# MCU_Radios_and_Sensors_SchDoc.net
KiCad netlist of a schematic drawn in Altium Designer
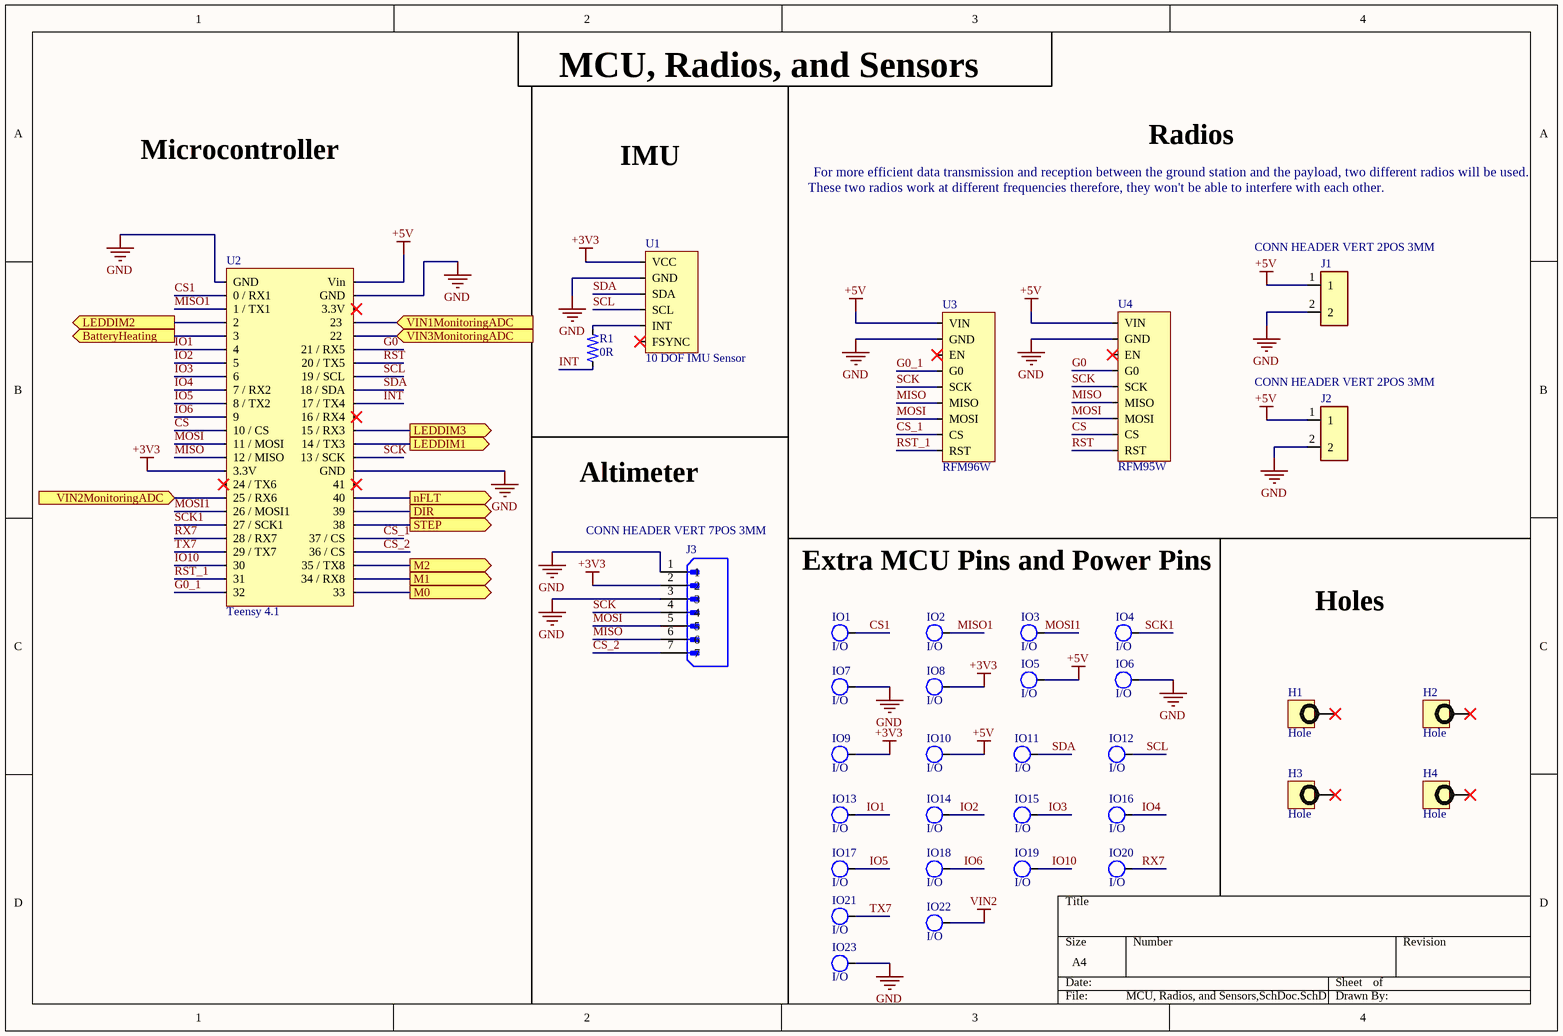
[diagram p0: MCU, Radios, and Sensors,SchDoc.SchDoc]

(export (version "E")
  (design (tool "Eeschema 10.0.6"))
  (components
    (comp (ref "H1") (value "Hole") (footprint "M3 Holes") (libsource (lib "MRT SCH Library") (part "Hole")))
    (comp (ref "H2") (value "Hole") (footprint "M3 Holes") (libsource (lib "MRT SCH Library") (part "Hole")))
    (comp (ref "H3") (value "Hole") (footprint "M3 Holes") (libsource (lib "MRT SCH Library") (part "Hole")))
    (comp (ref "H4") (value "Hole") (footprint "M3 Holes") (libsource (lib "MRT SCH Library") (part "Hole")))
    (comp (ref "IO1") (value "I/O") (footprint "Pins") (libsource (lib "Payload schlib") (part "I/O")))
    (comp (ref "IO2") (value "I/O") (footprint "Pins") (libsource (lib "Payload schlib") (part "I/O")))
    (comp (ref "IO3") (value "I/O") (footprint "Pins") (libsource (lib "Payload schlib") (part "I/O")))
    (comp (ref "IO4") (value "I/O") (footprint "Pins") (libsource (lib "Payload schlib") (part "I/O")))
    (comp (ref "IO5") (value "I/O") (footprint "Pins") (libsource (lib "Payload schlib") (part "I/O")))
    (comp (ref "IO6") (value "I/O") (footprint "Pins") (libsource (lib "Payload schlib") (part "I/O")))
    (comp (ref "IO7") (value "I/O") (footprint "Pins") (libsource (lib "Payload schlib") (part "I/O")))
    (comp (ref "IO8") (value "I/O") (footprint "Pins") (libsource (lib "Payload schlib") (part "I/O")))
    (comp (ref "IO9") (value "I/O") (footprint "Pins") (libsource (lib "Payload schlib") (part "I/O")))
    (comp (ref "IO10") (value "I/O") (footprint "Pins") (libsource (lib "Payload schlib") (part "I/O")))
    (comp (ref "IO11") (value "I/O") (footprint "Pins") (libsource (lib "Payload schlib") (part "I/O")))
    (comp (ref "IO12") (value "I/O") (footprint "Pins") (libsource (lib "Payload schlib") (part "I/O")))
    (comp (ref "IO13") (value "I/O") (footprint "Pins") (libsource (lib "Payload schlib") (part "I/O")))
    (comp (ref "IO14") (value "I/O") (footprint "Pins") (libsource (lib "Payload schlib") (part "I/O")))
    (comp (ref "IO15") (value "I/O") (footprint "Pins") (libsource (lib "Payload schlib") (part "I/O")))
    (comp (ref "IO16") (value "I/O") (footprint "Pins") (libsource (lib "Payload schlib") (part "I/O")))
    (comp (ref "IO17") (value "I/O") (footprint "Pins") (libsource (lib "Payload schlib") (part "I/O")))
    (comp (ref "IO18") (value "I/O") (footprint "Pins") (libsource (lib "Payload schlib") (part "I/O")))
    (comp (ref "IO19") (value "I/O") (footprint "Pins") (libsource (lib "Payload schlib") (part "I/O")))
    (comp (ref "IO20") (value "I/O") (footprint "Pins") (libsource (lib "Payload schlib") (part "I/O")))
    (comp (ref "IO21") (value "I/O") (footprint "Pins") (libsource (lib "Payload schlib") (part "I/O")))
    (comp (ref "IO22") (value "I/O") (footprint "Pins") (libsource (lib "Payload schlib") (part "I/O")))
    (comp (ref "IO23") (value "I/O") (footprint "Pins") (libsource (lib "Payload schlib") (part "I/O")))
    (comp (ref "J1")
      (value "CONN HEADER VERT 2POS 3MM")
      (footprint "CONN HEADER VERT 2POS 3MM")
      (description "Rectangular Power Connector, 2 Contact(s), Female, Solder Terminal")
      (fields (field (name "MF") "Molex") (field (name "MP") "0436500200"))
      (libsource (lib "Payload schlib") (part "0436500228"))
    )
    (comp (ref "J2")
      (value "CONN HEADER VERT 2POS 3MM")
      (footprint "CONN HEADER VERT 2POS 3MM")
      (description "Rectangular Power Connector, 2 Contact(s), Female, Solder Terminal")
      (fields (field (name "MF") "Molex") (field (name "MP") "0436500200"))
      (libsource (lib "Payload schlib") (part "0436500228"))
    )
    (comp (ref "J3")
      (value "CONN HEADER VERT 7POS 3MM")
      (footprint "MOLEX_436500728")
      (description "Connector Header Through Hole 7 position 0.118 (3.00mm)")
      (fields (field (name "MF") "Molex") (field (name "MP") "436500728"))
      (libsource (lib "Payload schlib") (part "436500728"))
    )
    (comp (ref "R1")
      (value "0R")
      (footprint "res 0805")
      (fields
        (field (name "MP") "2-2176053-2")
        (field (name "MF") "TE Connectivity")
        (field (name "TOLERANCE") "1%")
      )
      (libsource (lib "Payload schlib") (part "Resistor 0805"))
    )
    (comp (ref "U1")
      (value "10 DOF IMU Sensor")
      (footprint "10 DOF IMU Sensor")
      (description "10 DOF IMU Sensor, ICM20948 Onboard, Low Power, High Precision")
      (libsource (lib "Payload schlib") (part "10 DOF IMU Sensor"))
    )
    (comp (ref "U2")
      (value "Teensy 4.1")
      (footprint "Teensy 4.1")
      (description "iMXRT1062 Microcontroller Development Board 600MHz CPU 1GB RAM 8MB Flash")
      (fields (field (name "MANUFACTURER") "SparkFun") (field (name "MANUFACTURER PART NUMBER") "DEV-16771"))
      (libsource (lib "Payload schlib") (part "Teensy 4.1"))
    )
    (comp (ref "U3")
      (value "RFM96W")
      (footprint "RFM95W")
      (description "Banana Plug; Female to Multi-Stacking Banana Plug; Nickel Plated Brass")
      (fields
        (field (name "MANUFACTURER") "Adafruit Industries")
        (field (name "MANUFACTURER PART NUMBER") "3072")
      )
      (libsource (lib "Payload schlib") (part "RFM96W"))
    )
    (comp (ref "U4")
      (value "RFM95W")
      (footprint "RFM95W")
      (description "Adafruit RFM95W LoRa Radio Transceiver Breakout - 868 or 915 MHz")
      (fields
        (field (name "MANUFACTURER") "Adafruit Industries")
        (field (name "MANUFACTURER PART NUMBER") "3072")
      )
      (libsource (lib "Payload schlib") (part "RFM95W"))
    )
  )
  (nets
    (net (code "1") (name "+3V3") (class "Default")
      (node (ref "IO8") (pin "1") (pinfunction "1_1") (pintype "passive"))
      (node (ref "IO9") (pin "1") (pinfunction "1_1") (pintype "passive"))
      (node (ref "J3") (pin "2") (pinfunction "2_2") (pintype "passive"))
      (node (ref "U1") (pin "1") (pinfunction "VCC_1") (pintype "passive"))
      (node (ref "U2") (pin "15") (pinfunction "3.3V_15") (pintype "passive"))
    )
    (net (code "2") (name "+5V") (class "Default")
      (node (ref "IO10") (pin "1") (pinfunction "1_1") (pintype "passive"))
      (node (ref "IO5") (pin "1") (pinfunction "1_1") (pintype "passive"))
      (node (ref "J1") (pin "1") (pinfunction "1_1") (pintype "passive"))
      (node (ref "J2") (pin "1") (pinfunction "1_1") (pintype "passive"))
      (node (ref "U2") (pin "48") (pinfunction "Vin_48") (pintype "passive"))
      (node (ref "U3") (pin "1") (pinfunction "VIN_1") (pintype "passive"))
      (node (ref "U4") (pin "1") (pinfunction "VIN_1") (pintype "passive"))
    )
    (net (code "3") (name "/BatteryHeating") (class "Default")
      (node (ref "U2") (pin "5") (pinfunction "3_5") (pintype "passive"))
    )
    (net (code "4") (name "/CS") (class "Default")
      (node (ref "U2") (pin "12") (pinfunction "10_/_CS_12") (pintype "passive"))
      (node (ref "U4") (pin "8") (pinfunction "CS_8") (pintype "passive"))
    )
    (net (code "5") (name "/CS1") (class "Default")
      (node (ref "IO1") (pin "1") (pinfunction "1_1") (pintype "passive"))
      (node (ref "U2") (pin "2") (pinfunction "0_/_RX1_2") (pintype "passive"))
    )
    (net (code "6") (name "/CS_1") (class "Default")
      (node (ref "U2") (pin "29") (pinfunction "37_/_CS_29") (pintype "passive"))
      (node (ref "U3") (pin "8") (pinfunction "CS_8") (pintype "passive"))
    )
    (net (code "7") (name "/CS_2") (class "Default")
      (node (ref "J3") (pin "7") (pinfunction "7_7") (pintype "passive"))
      (node (ref "U2") (pin "28") (pinfunction "36_/_CS_28") (pintype "passive"))
    )
    (net (code "8") (name "/DIR") (class "Default")
      (node (ref "U2") (pin "31") (pinfunction "39_31") (pintype "passive"))
    )
    (net (code "9") (name "/G0") (class "Default")
      (node (ref "U2") (pin "43") (pinfunction "21_/_RX5_43") (pintype "passive"))
      (node (ref "U4") (pin "4") (pinfunction "G0_4") (pintype "passive"))
    )
    (net (code "10") (name "/G0_1") (class "Default")
      (node (ref "U2") (pin "24") (pinfunction "32_24") (pintype "passive"))
      (node (ref "U3") (pin "4") (pinfunction "G0_4") (pintype "passive"))
    )
    (net (code "11") (name "/INT") (class "Default")
      (node (ref "R1") (pin "1") (pinfunction "1_1") (pintype "passive"))
      (node (ref "U2") (pin "39") (pinfunction "17_/_TX4_39") (pintype "passive"))
    )
    (net (code "12") (name "/IO1") (class "Default")
      (node (ref "IO13") (pin "1") (pinfunction "1_1") (pintype "passive"))
      (node (ref "U2") (pin "6") (pinfunction "4_6") (pintype "passive"))
    )
    (net (code "13") (name "/IO2") (class "Default")
      (node (ref "IO14") (pin "1") (pinfunction "1_1") (pintype "passive"))
      (node (ref "U2") (pin "7") (pinfunction "5_7") (pintype "passive"))
    )
    (net (code "14") (name "/IO3") (class "Default")
      (node (ref "IO15") (pin "1") (pinfunction "1_1") (pintype "passive"))
      (node (ref "U2") (pin "8") (pinfunction "6_8") (pintype "passive"))
    )
    (net (code "15") (name "/IO4") (class "Default")
      (node (ref "IO16") (pin "1") (pinfunction "1_1") (pintype "passive"))
      (node (ref "U2") (pin "9") (pinfunction "7_/_RX2_9") (pintype "passive"))
    )
    (net (code "16") (name "/IO5") (class "Default")
      (node (ref "IO17") (pin "1") (pinfunction "1_1") (pintype "passive"))
      (node (ref "U2") (pin "10") (pinfunction "8_/_TX2_10") (pintype "passive"))
    )
    (net (code "17") (name "/IO6") (class "Default")
      (node (ref "IO18") (pin "1") (pinfunction "1_1") (pintype "passive"))
      (node (ref "U2") (pin "11") (pinfunction "9_11") (pintype "passive"))
    )
    (net (code "18") (name "/IO10") (class "Default")
      (node (ref "IO19") (pin "1") (pinfunction "1_1") (pintype "passive"))
      (node (ref "U2") (pin "22") (pinfunction "30_22") (pintype "passive"))
    )
    (net (code "19") (name "/LEDDIM1") (class "Default")
      (node (ref "U2") (pin "36") (pinfunction "14_/_TX3_36") (pintype "passive"))
    )
    (net (code "20") (name "/LEDDIM2") (class "Default")
      (node (ref "U2") (pin "4") (pinfunction "2_4") (pintype "passive"))
    )
    (net (code "21") (name "/LEDDIM3") (class "Default")
      (node (ref "U2") (pin "37") (pinfunction "15_/_RX3_37") (pintype "passive"))
    )
    (net (code "22") (name "/M0") (class "Default")
      (node (ref "U2") (pin "25") (pinfunction "33_25") (pintype "passive"))
    )
    (net (code "23") (name "/M1") (class "Default")
      (node (ref "U2") (pin "26") (pinfunction "34_/_RX8_26") (pintype "passive"))
    )
    (net (code "24") (name "/M2") (class "Default")
      (node (ref "U2") (pin "27") (pinfunction "35_/_TX8_27") (pintype "passive"))
    )
    (net (code "25") (name "/MISO") (class "Default")
      (node (ref "J3") (pin "6") (pinfunction "6_6") (pintype "passive"))
      (node (ref "U2") (pin "14") (pinfunction "12_/_MISO_14") (pintype "passive"))
      (node (ref "U3") (pin "6") (pinfunction "MISO_6") (pintype "passive"))
      (node (ref "U4") (pin "6") (pinfunction "MISO_6") (pintype "passive"))
    )
    (net (code "26") (name "/MISO1") (class "Default")
      (node (ref "IO2") (pin "1") (pinfunction "1_1") (pintype "passive"))
      (node (ref "U2") (pin "3") (pinfunction "1_/_TX1_3") (pintype "passive"))
    )
    (net (code "27") (name "/MOSI") (class "Default")
      (node (ref "J3") (pin "5") (pinfunction "5_5") (pintype "passive"))
      (node (ref "U2") (pin "13") (pinfunction "11_/_MOSI_13") (pintype "passive"))
      (node (ref "U3") (pin "7") (pinfunction "MOSI_7") (pintype "passive"))
      (node (ref "U4") (pin "7") (pinfunction "MOSI_7") (pintype "passive"))
    )
    (net (code "28") (name "/MOSI1") (class "Default")
      (node (ref "IO3") (pin "1") (pinfunction "1_1") (pintype "passive"))
      (node (ref "U2") (pin "18") (pinfunction "26_/_MOSI1_18") (pintype "passive"))
    )
    (net (code "29") (name "/RST") (class "Default")
      (node (ref "U2") (pin "42") (pinfunction "20_/_TX5_42") (pintype "passive"))
      (node (ref "U4") (pin "9") (pinfunction "RST_9") (pintype "passive"))
    )
    (net (code "30") (name "/RST_1") (class "Default")
      (node (ref "U2") (pin "23") (pinfunction "31_23") (pintype "passive"))
      (node (ref "U3") (pin "9") (pinfunction "RST_9") (pintype "passive"))
    )
    (net (code "31") (name "/RX7") (class "Default")
      (node (ref "IO20") (pin "1") (pinfunction "1_1") (pintype "passive"))
      (node (ref "U2") (pin "20") (pinfunction "28_/_RX7_20") (pintype "passive"))
    )
    (net (code "32") (name "/SCK") (class "Default")
      (node (ref "J3") (pin "4") (pinfunction "4_4") (pintype "passive"))
      (node (ref "U2") (pin "35") (pinfunction "13_/_SCK_35") (pintype "passive"))
      (node (ref "U3") (pin "5") (pinfunction "SCK_5") (pintype "passive"))
      (node (ref "U4") (pin "5") (pinfunction "SCK_5") (pintype "passive"))
    )
    (net (code "33") (name "/SCK1") (class "Default")
      (node (ref "IO4") (pin "1") (pinfunction "1_1") (pintype "passive"))
      (node (ref "U2") (pin "19") (pinfunction "27_/_SCK1_19") (pintype "passive"))
    )
    (net (code "34") (name "/SCL") (class "Default")
      (node (ref "IO12") (pin "1") (pinfunction "1_1") (pintype "passive"))
      (node (ref "U1") (pin "4") (pinfunction "SCL_4") (pintype "passive"))
      (node (ref "U2") (pin "41") (pinfunction "19_/_SCL_41") (pintype "passive"))
    )
    (net (code "35") (name "/SDA") (class "Default")
      (node (ref "IO11") (pin "1") (pinfunction "1_1") (pintype "passive"))
      (node (ref "U1") (pin "3") (pinfunction "SDA_3") (pintype "passive"))
      (node (ref "U2") (pin "40") (pinfunction "18_/_SDA_40") (pintype "passive"))
    )
    (net (code "36") (name "/STEP") (class "Default")
      (node (ref "U2") (pin "30") (pinfunction "38_30") (pintype "passive"))
    )
    (net (code "37") (name "/TX7") (class "Default")
      (node (ref "IO21") (pin "1") (pinfunction "1_1") (pintype "passive"))
      (node (ref "U2") (pin "21") (pinfunction "29_/_TX7_21") (pintype "passive"))
    )
    (net (code "38") (name "/VIN1MonitoringADC") (class "Default")
      (node (ref "U2") (pin "45") (pinfunction "23_45") (pintype "passive"))
    )
    (net (code "39") (name "/VIN2MonitoringADC") (class "Default")
      (node (ref "U2") (pin "17") (pinfunction "25_/_RX6_17") (pintype "passive"))
    )
    (net (code "40") (name "/VIN3MonitoringADC") (class "Default")
      (node (ref "U2") (pin "44") (pinfunction "22_44") (pintype "passive"))
    )
    (net (code "41") (name "/nFLT") (class "Default")
      (node (ref "U2") (pin "32") (pinfunction "40_32") (pintype "passive"))
    )
    (net (code "42") (name "GND") (class "Default")
      (node (ref "IO23") (pin "1") (pinfunction "1_1") (pintype "passive"))
      (node (ref "IO6") (pin "1") (pinfunction "1_1") (pintype "passive"))
      (node (ref "IO7") (pin "1") (pinfunction "1_1") (pintype "passive"))
      (node (ref "J1") (pin "2") (pinfunction "2_2") (pintype "passive"))
      (node (ref "J2") (pin "2") (pinfunction "2_2") (pintype "passive"))
      (node (ref "J3") (pin "1") (pinfunction "1_1") (pintype "passive"))
      (node (ref "J3") (pin "3") (pinfunction "3_3") (pintype "passive"))
      (node (ref "U1") (pin "2") (pinfunction "GND_2") (pintype "passive"))
      (node (ref "U2") (pin "1") (pinfunction "GND_1") (pintype "passive"))
      (node (ref "U2") (pin "34") (pinfunction "GND_34") (pintype "passive"))
      (node (ref "U2") (pin "47") (pinfunction "GND_47") (pintype "passive"))
      (node (ref "U3") (pin "2") (pinfunction "GND_2") (pintype "passive"))
      (node (ref "U4") (pin "2") (pinfunction "GND_2") (pintype "passive"))
    )
    (net (code "43") (name "Net-(U1-INT)") (class "Default")
      (node (ref "R1") (pin "2") (pinfunction "2_2") (pintype "passive"))
      (node (ref "U1") (pin "5") (pinfunction "INT_5") (pintype "passive"))
    )
    (net (code "44") (name "VIN2") (class "Default")
      (node (ref "IO22") (pin "1") (pinfunction "1_1") (pintype "passive"))
    )
    (net (code "45") (name "unconnected-(H1-TERMINAL-Pad1)") (class "Default")
      (node (ref "H1") (pin "1") (pinfunction "TERMINAL_1") (pintype "passive+no_connect"))
    )
    (net (code "46") (name "unconnected-(H2-TERMINAL-Pad1)") (class "Default")
      (node (ref "H2") (pin "1") (pinfunction "TERMINAL_1") (pintype "passive+no_connect"))
    )
    (net (code "47") (name "unconnected-(H3-TERMINAL-Pad1)") (class "Default")
      (node (ref "H3") (pin "1") (pinfunction "TERMINAL_1") (pintype "passive+no_connect"))
    )
    (net (code "48") (name "unconnected-(H4-TERMINAL-Pad1)") (class "Default")
      (node (ref "H4") (pin "1") (pinfunction "TERMINAL_1") (pintype "passive+no_connect"))
    )
    (net (code "49") (name "unconnected-(U1-FSYNC-Pad6)") (class "Default")
      (node (ref "U1") (pin "6") (pinfunction "FSYNC_6") (pintype "passive+no_connect"))
    )
    (net (code "50") (name "unconnected-(U2-3.3V-Pad46)") (class "Default")
      (node (ref "U2") (pin "46") (pinfunction "3.3V_46") (pintype "passive+no_connect"))
    )
    (net (code "51") (name "unconnected-(U2-16_{slash}_RX4-Pad38)") (class "Default")
      (node (ref "U2") (pin "38") (pinfunction "16_/_RX4_38") (pintype "passive+no_connect"))
    )
    (net (code "52") (name "unconnected-(U2-24_{slash}_TX6-Pad16)") (class "Default")
      (node (ref "U2") (pin "16") (pinfunction "24_/_TX6_16") (pintype "passive+no_connect"))
    )
    (net (code "53") (name "unconnected-(U2-41-Pad33)") (class "Default")
      (node (ref "U2") (pin "33") (pinfunction "41_33") (pintype "passive+no_connect"))
    )
    (net (code "54") (name "unconnected-(U3-EN-Pad3)") (class "Default")
      (node (ref "U3") (pin "3") (pinfunction "EN_3") (pintype "passive+no_connect"))
    )
    (net (code "55") (name "unconnected-(U4-EN-Pad3)") (class "Default")
      (node (ref "U4") (pin "3") (pinfunction "EN_3") (pintype "passive+no_connect"))
    )
  )
)
